# INPUT_POWER.net
KiCad netlist of a schematic drawn in Altium Designer
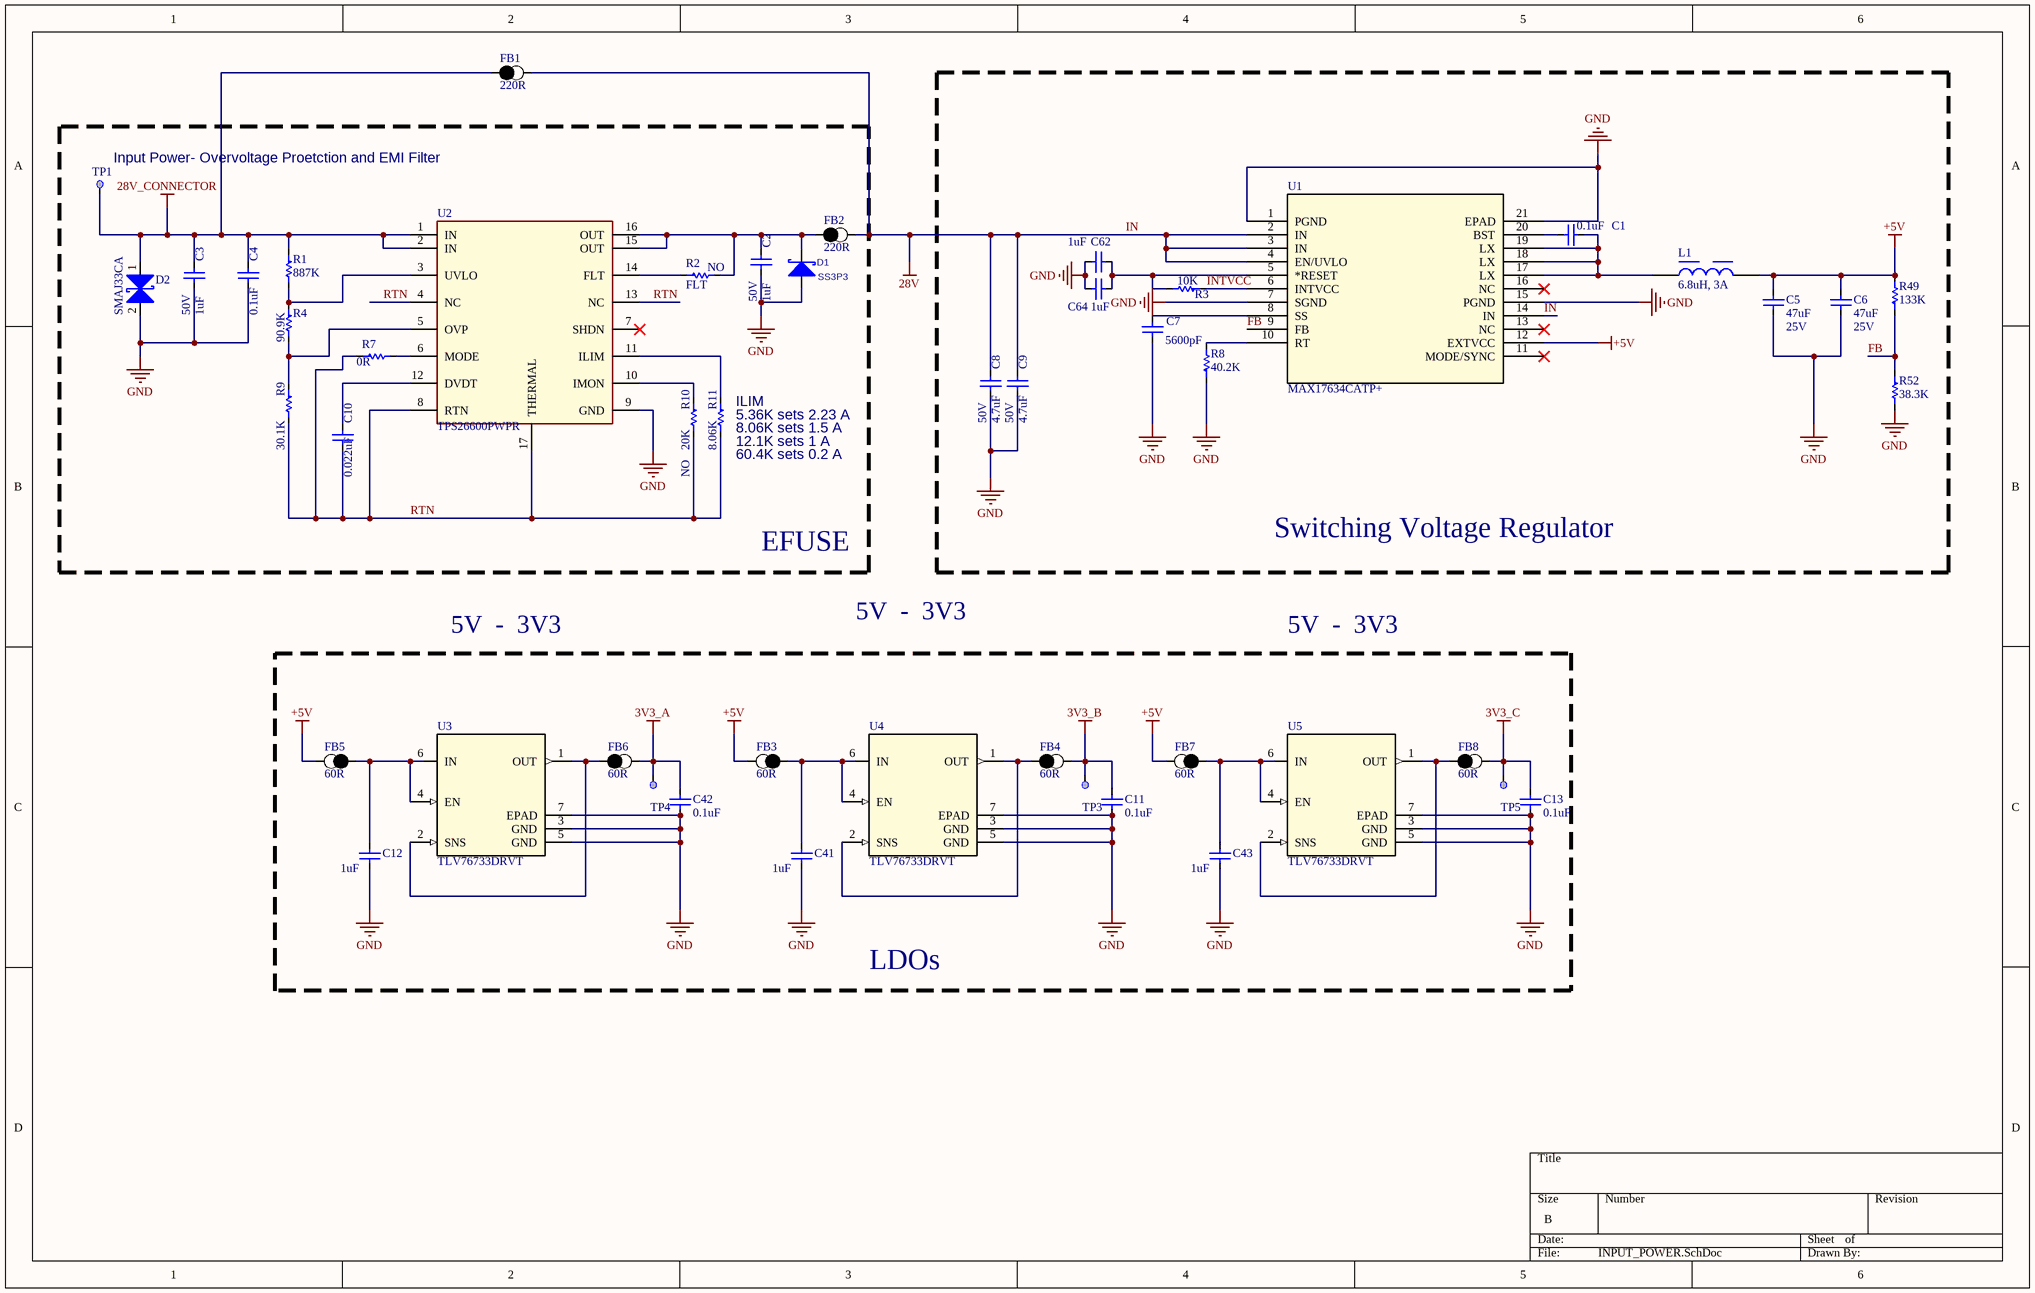
[diagram p0: INPUT_POWER.SchDoc]

(export (version "E")
  (design (tool "Eeschema 10.0.6"))
  (components
    (comp (ref "C1")
      (value "0.1uF")
      (footprint "CAPC1005-0402X55N")
      (description "CAP CER 0.1UF 16V X7R 0402")
      (fields (field (name "MANUFACTURER") "Samsung Electro-Mechanics") (field (name "VOLTAGE") "16V"))
      (libsource (lib "ANTSIS_PASSIVE") (part "CAP 0.1uF_0402"))
    )
    (comp (ref "C2")
      (value "1uF")
      (footprint "CAPC2012-0805X80N")
      (description "CAP CER 1UF 50V X5R 0805")
      (fields
        (field (name "MANUFACTURER") "Taiyo Yuden")
        (field (name "VOLTAGE") "50V")
        (field (name "TOLERANCE") "-55°C ~ 125°C")
      )
      (libsource (lib "capacitor") (part "Capacitor Ceramic"))
    )
    (comp (ref "C3")
      (value "1uF")
      (footprint "CAPC2012-0805X80N")
      (description "CAP CER 1UF 50V X5R 0805")
      (fields
        (field (name "MANUFACTURER") "Taiyo Yuden")
        (field (name "VOLTAGE") "50V")
        (field (name "TOLERANCE") "-55°C ~ 125°C")
      )
      (libsource (lib "capacitor") (part "Capacitor Ceramic"))
    )
    (comp (ref "C4")
      (value "0.1uF")
      (footprint "CAPC2012-0805X110N")
      (description "CAP CER 0.1UF 100V X7R 0805")
      (fields (field (name "MANUFACTURER") "Murata Electronics") (field (name "VOLTAGE") "100V"))
      (libsource (lib "capacitor") (part "Capacitor Ceramic"))
    )
    (comp (ref "C5")
      (value "47uF")
      (footprint "CAPC2012-0805X150N")
      (description "CAP CER 22UF 25V X5R 0805")
      (fields
        (field (name "MANUFACTURER") "Murata Electronics")
        (field (name "TOLERANCE") "-55°C ~ 85°C")
        (field (name "VOLTAGE") "25V")
      )
      (libsource (lib "Video_Encoder_SDI") (part "CAP CER 22UF 0805 25V"))
    )
    (comp (ref "C6")
      (value "47uF")
      (footprint "CAPC2012-0805X150N")
      (description "CAP CER 22UF 25V X5R 0805")
      (fields
        (field (name "MANUFACTURER") "Murata Electronics")
        (field (name "TOLERANCE") "-55°C ~ 85°C")
        (field (name "VOLTAGE") "25V")
      )
      (libsource (lib "Video_Encoder_SDI") (part "CAP CER 22UF 0805 25V"))
    )
    (comp (ref "C7")
      (value "5600pF")
      (footprint "CAPC1005-0402X55N")
      (description "CAP CER 5600PF 25V X7R 0402")
      (fields (field (name "MANUFACTURER") "Murata Electronics") (field (name "VOLTAGE") "25V"))
      (libsource (lib "ANTSIS_PASSIVE") (part "CAP 10nF_0402"))
    )
    (comp (ref "C8")
      (value "4.7uF")
      (footprint "CAPC2012-0805X80N")
      (description "CAP CER 1UF 50V X5R 0805")
      (fields
        (field (name "MANUFACTURER") "Taiyo Yuden")
        (field (name "VOLTAGE") "50V")
        (field (name "TOLERANCE") "-55°C ~ 125°C")
      )
      (libsource (lib "capacitor") (part "Capacitor Ceramic"))
    )
    (comp (ref "C9")
      (value "4.7uF")
      (footprint "CAPC2012-0805X80N")
      (description "CAP CER 1UF 50V X5R 0805")
      (fields
        (field (name "MANUFACTURER") "Taiyo Yuden")
        (field (name "VOLTAGE") "50V")
        (field (name "TOLERANCE") "-55°C ~ 125°C")
      )
      (libsource (lib "capacitor") (part "Capacitor Ceramic"))
    )
    (comp (ref "C10")
      (value "0.022uF")
      (footprint "CAPC1608-0603X90N")
      (description "CAP CER 0.022UF 16V X7R 0603")
      (fields (field (name "MANUFACTURER") "Yageo") (field (name "VOLTAGE") "16V"))
      (libsource (lib "capacitor") (part "Capacitor Ceramic"))
    )
    (comp (ref "C11")
      (value "0.1uF")
      (footprint "CAPC1608-0603X90N")
      (description "CAP CER 0.1UF 50V X7R 0603")
      (fields (field (name "MANUFACTURER") "Samsung Electro-Mechanics") (field (name "VOLTAGE") "50V"))
      (libsource (lib "ANTSIS_PASSIVE") (part "CAP 0.1uF"))
    )
    (comp (ref "C12")
      (value "1uF")
      (footprint "CAPC1608-0603X90N")
      (description "CAP CER 1UF 25V X7R 0603")
      (fields (field (name "MANUFACTURER") "Samsung Electro-Mechanics") (field (name "VOLTAGE") "25V"))
      (libsource (lib "ANTSIS_PASSIVE") (part "CAP 1uF"))
    )
    (comp (ref "C13")
      (value "0.1uF")
      (footprint "CAPC1608-0603X90N")
      (description "CAP CER 0.1UF 50V X7R 0603")
      (fields (field (name "MANUFACTURER") "Samsung Electro-Mechanics") (field (name "VOLTAGE") "50V"))
      (libsource (lib "ANTSIS_PASSIVE") (part "CAP 0.1uF"))
    )
    (comp (ref "C41")
      (value "1uF")
      (footprint "CAPC1608-0603X90N")
      (description "CAP CER 1UF 25V X7R 0603")
      (fields (field (name "MANUFACTURER") "Samsung Electro-Mechanics") (field (name "VOLTAGE") "25V"))
      (libsource (lib "ANTSIS_PASSIVE") (part "CAP 1uF"))
    )
    (comp (ref "C42")
      (value "0.1uF")
      (footprint "CAPC1608-0603X90N")
      (description "CAP CER 0.1UF 50V X7R 0603")
      (fields (field (name "MANUFACTURER") "Samsung Electro-Mechanics") (field (name "VOLTAGE") "50V"))
      (libsource (lib "ANTSIS_PASSIVE") (part "CAP 0.1uF"))
    )
    (comp (ref "C43")
      (value "1uF")
      (footprint "CAPC1608-0603X90N")
      (description "CAP CER 1UF 25V X7R 0603")
      (fields (field (name "MANUFACTURER") "Samsung Electro-Mechanics") (field (name "VOLTAGE") "25V"))
      (libsource (lib "ANTSIS_PASSIVE") (part "CAP 1uF"))
    )
    (comp (ref "C62")
      (value "1uF")
      (footprint "CAPC1608-0603X90N")
      (description "CAP CER 1UF 25V X7R 0603")
      (fields (field (name "MANUFACTURER") "Samsung Electro-Mechanics") (field (name "VOLTAGE") "25V"))
      (libsource (lib "ANTSIS_PASSIVE") (part "CAP 1uF"))
    )
    (comp (ref "C64")
      (value "1uF")
      (footprint "CAPC1608-0603X90N")
      (description "CAP CER 1UF 25V X7R 0603")
      (fields (field (name "MANUFACTURER") "Samsung Electro-Mechanics") (field (name "VOLTAGE") "25V"))
      (libsource (lib "ANTSIS_PASSIVE") (part "CAP 1uF"))
    )
    (comp (ref "D1")
      (value "SS3P3")
      (footprint "DO-220AA (SMP)")
      (description "DIODE SCHOTTKY 40V 3A DO220AA")
      (fields
        (field (name "MANUFACTURER") "Vishay Semiconductor Diodes Division")
        (field (name "VOLTAGE") "40V")
      )
      (libsource (lib "Ixora") (part "D-Vishay-SS3P3-E3/84A-Schottky"))
    )
    (comp (ref "D2")
      (value "SMAJ33CA")
      (footprint "DO-214AC")
      (description "TVS DIODE 33V 53.3V DO214AC")
      (fields
        (field (name "MANUFACTURER") "ON Semiconductor")
        (field (name "TOLERANCE") "-65°C ~ 150°C (TJ)")
      )
      (libsource (lib "ANTSIS_DIODE_TRANSISTOR") (part "SMAJ33CA"))
    )
    (comp (ref "FB1")
      (value "220R")
      (footprint "INDC2012-0805X90N")
      (description "FERRITE BEAD 220 OHM 0805 1LN")
      (fields (field (name "MANUFACTURER") "Murata Electronics") (field (name "VOLTAGE") "2A"))
      (libsource (lib "Inductors & Transformers") (part "Inductor EMI suppresion"))
    )
    (comp (ref "FB2")
      (value "220R")
      (footprint "INDC2012-0805X90N")
      (description "FERRITE BEAD 220 OHM 0805 1LN")
      (fields (field (name "MANUFACTURER") "Murata Electronics") (field (name "VOLTAGE") "2A"))
      (libsource (lib "Inductors & Transformers") (part "Inductor EMI suppresion"))
    )
    (comp (ref "FB3")
      (value "60R")
      (footprint "INDC1608-0603X80N")
      (description "FERRITE BEAD 60 OHM 0603 1LN")
      (fields (field (name "MANUFACTURER") "Würth Elektronik") (field (name "TOLERANCE") "-55°C ~ 125°C"))
      (libsource (lib "ANTSIS_PASSIVE") (part "FERRITE 60R 3A"))
    )
    (comp (ref "FB4")
      (value "60R")
      (footprint "INDC1608-0603X80N")
      (description "FERRITE BEAD 60 OHM 0603 1LN")
      (fields (field (name "MANUFACTURER") "Würth Elektronik") (field (name "TOLERANCE") "-55°C ~ 125°C"))
      (libsource (lib "ANTSIS_PASSIVE") (part "FERRITE 60R 3A"))
    )
    (comp (ref "FB5")
      (value "60R")
      (footprint "INDC1608-0603X80N")
      (description "FERRITE BEAD 60 OHM 0603 1LN")
      (fields (field (name "MANUFACTURER") "Würth Elektronik") (field (name "TOLERANCE") "-55°C ~ 125°C"))
      (libsource (lib "ANTSIS_PASSIVE") (part "FERRITE 60R 3A"))
    )
    (comp (ref "FB6")
      (value "60R")
      (footprint "INDC1608-0603X80N")
      (description "FERRITE BEAD 60 OHM 0603 1LN")
      (fields (field (name "MANUFACTURER") "Würth Elektronik") (field (name "TOLERANCE") "-55°C ~ 125°C"))
      (libsource (lib "ANTSIS_PASSIVE") (part "FERRITE 60R 3A"))
    )
    (comp (ref "FB7")
      (value "60R")
      (footprint "INDC1608-0603X80N")
      (description "FERRITE BEAD 60 OHM 0603 1LN")
      (fields (field (name "MANUFACTURER") "Würth Elektronik") (field (name "TOLERANCE") "-55°C ~ 125°C"))
      (libsource (lib "ANTSIS_PASSIVE") (part "FERRITE 60R 3A"))
    )
    (comp (ref "FB8")
      (value "60R")
      (footprint "INDC1608-0603X80N")
      (description "FERRITE BEAD 60 OHM 0603 1LN")
      (fields (field (name "MANUFACTURER") "Würth Elektronik") (field (name "TOLERANCE") "-55°C ~ 125°C"))
      (libsource (lib "ANTSIS_PASSIVE") (part "FERRITE 60R 3A"))
    )
    (comp (ref "L1")
      (value "6.8uH, 3A")
      (footprint "WE-MAIA_4030")
      (description "WE-MAIA SMT Power Inductor, size 4030, 6.8uH, 3A, 74mOhm")
      (fields
        (field (name "MANUFACTURER PART NUMBER") "78438357068")
        (field (name "MANUFACTURER") "Wurth Elektronik")
      )
      (libsource (lib "Altium_WE-MAIA (rev20c)") (part "78438357068"))
    )
    (comp (ref "R1")
      (value "887K")
      (footprint "RESC1608-0603X50N")
      (description "RES SMD 887K OHM 1% 1/10W 0603")
      (fields (field (name "MANUFACTURER") "Vishay Dale") (field (name "TOLERANCE") "-55°C ~ 155°C"))
      (libsource (lib "resistor") (part "Resistor SMD"))
    )
    (comp (ref "R2")
      (value "FLT")
      (footprint "RESC1608-0603X50N")
      (description "RES SMD 12.1K OHM 1% 1/10W 0603")
      (fields (field (name "POPULATED") "NO") (field (name "TOLERANCE") "-55°C ~ 155°C"))
      (libsource (lib "resistor") (part "Resistor SMD"))
    )
    (comp (ref "R3")
      (value "10K")
      (footprint "RESC1005-0402X35N")
      (description "RES SMD 10K OHM 1% 1/10W 0402")
      (fields (field (name "MANUFACTURER") "Yageo") (field (name "TOLERANCE") "5%"))
      (libsource (lib "ANTSIS_PASSIVE") (part "RESISTOR 10K_0402"))
    )
    (comp (ref "R4")
      (value "90.9K")
      (footprint "RESC1608-0603X50N")
      (description "RES SMD 90.9K OHM 1% 1/10W 0603")
      (fields (field (name "MANUFACTURER") "Vishay Dale") (field (name "TOLERANCE") "-55°C ~ 155°C"))
      (libsource (lib "resistor") (part "Resistor SMD"))
    )
    (comp (ref "R7")
      (value "0R")
      (footprint "RESC1608-0603X50N")
      (description "RES SMD 0 OHM JUMPER 1/10W 0603")
      (fields (field (name "MANUFACTURER") "Yageo") (field (name "TOLERANCE") "-55°C ~ 155°C"))
      (libsource (lib "resistor") (part "Resistor SMD"))
    )
    (comp (ref "R8")
      (value "40.2K")
      (footprint "RESC1608-0603X50N")
      (description "RES SMD 0 OHM JUMPER 1/10W 0603")
      (fields (field (name "MANUFACTURER") "Yageo"))
      (libsource (lib "ANTSIS_PASSIVE") (part "RESISTOR 0R"))
    )
    (comp (ref "R9")
      (value "30.1K")
      (footprint "RESC1608-0603X50N")
      (description "RES SMD 30.1K OHM 1% 1/10W 0603")
      (fields (field (name "MANUFACTURER") "Vishay Dale") (field (name "TOLERANCE") "-55°C ~ 155°C"))
      (libsource (lib "resistor") (part "Resistor SMD"))
    )
    (comp (ref "R10")
      (value "20K")
      (footprint "RESC1608-0603X50N")
      (description "RES SMD 20K OHM 1% 1/10W 0603")
      (fields
        (field (name "POPULATED") "NO")
        (field (name "MANUFACTURER") "Vishay Dale")
        (field (name "TOLERANCE") "-55°C ~ 155°C")
      )
      (libsource (lib "resistor") (part "Resistor SMD"))
    )
    (comp (ref "R11")
      (value "8.06K")
      (footprint "RESC1608-0603X50N")
      (description "RES SMD 8.06 OHM 1% 1/10W 0603")
      (fields (field (name "MANUFACTURER") "Vishay Dale") (field (name "TOLERANCE") "-55°C ~ 155°C"))
      (libsource (lib "resistor") (part "Resistor SMD"))
    )
    (comp (ref "R49")
      (value "133K")
      (footprint "RESC1608-0603X50N")
      (description "RES SMD 133K OHM 1% 1/4W 0603")
      (fields (field (name "MANUFACTURER") "Vishay Dale") (field (name "TOLERANCE") "1%"))
      (libsource (lib "ANTSIS_PASSIVE") (part "RESISTOR 143K"))
    )
    (comp (ref "R52")
      (value "38.3K")
      (footprint "RESC1608-0603X50N")
      (description "RES 38.3K OHM 1% 1/10W 0603")
      (fields (field (name "MANUFACTURER") "Stackpole Electronics Inc") (field (name "TOLERANCE") "1%"))
      (libsource (lib "ANTSIS_PASSIVE") (part "RESISTOR 143K"))
    )
    (comp (ref "TP1")
      (value "TP")
      (footprint "TP-OCTAGONAL")
      (description "Test point")
      (libsource (lib "ANTSIS_AUX_PART") (part "TP"))
    )
    (comp (ref "TP3")
      (value "TP")
      (footprint "TP-OCTAGONAL")
      (description "Test point")
      (libsource (lib "ANTSIS_AUX_PART") (part "TP"))
    )
    (comp (ref "TP4")
      (value "TP")
      (footprint "TP-OCTAGONAL")
      (description "Test point")
      (libsource (lib "ANTSIS_AUX_PART") (part "TP"))
    )
    (comp (ref "TP5")
      (value "TP")
      (footprint "TP-OCTAGONAL")
      (description "Test point")
      (libsource (lib "ANTSIS_AUX_PART") (part "TP"))
    )
    (comp (ref "U1")
      (value "MAX17634CATP+")
      (footprint "max17633")
      (description "IC REG BUCK ADJ 4.25A")
      (fields
        (field (name "MANUFACTURER_PART_NUMBER") "MAX17633CATP+")
        (field (name "COPYRIGHT") "Copyright (C) 2021 Ultra Librarian. All rights reserved.")
      )
      (libsource (lib "MAX17633CATP&plus_") (part "MAX17633CATP+"))
    )
    (comp (ref "U2")
      (value "TPS26600PWPR")
      (footprint "TSSOP65P640-16N-2.74MM T.PAD")
      (description "IC PWR MGMT EFUSE 60V 16HTSSOP")
      (fields
        (field (name "MANUFACTURER") "Texas Instruments")
        (field (name "TOLERANCE") "-40°C ~ 125°C (TJ)")
      )
      (libsource (lib "TI") (part "TPS26600"))
    )
    (comp (ref "U3")
      (value "TLV76733DRVT")
      (footprint "SON65P200X200X80-7N")
      (description "No Description Available")
      (fields (field (name "COPYRIGHT") "Copyright (C) 2021 Ultra Librarian. All rights reserved."))
      (libsource (lib "TLV76733DRVT") (part "TLV76733DRVT"))
    )
    (comp (ref "U4")
      (value "TLV76733DRVT")
      (footprint "SON65P200X200X80-7N")
      (description "No Description Available")
      (fields (field (name "COPYRIGHT") "Copyright (C) 2021 Ultra Librarian. All rights reserved."))
      (libsource (lib "TLV76733DRVT") (part "TLV76733DRVT"))
    )
    (comp (ref "U5")
      (value "TLV76733DRVT")
      (footprint "SON65P200X200X80-7N")
      (description "No Description Available")
      (fields (field (name "COPYRIGHT") "Copyright (C) 2021 Ultra Librarian. All rights reserved."))
      (libsource (lib "TLV76733DRVT") (part "TLV76733DRVT"))
    )
  )
  (nets
    (net (code "1") (name "+5V") (class "Default")
      (node (ref "C5") (pin "2") (pinfunction "2_2") (pintype "passive"))
      (node (ref "C6") (pin "2") (pinfunction "2_2") (pintype "passive"))
      (node (ref "FB3") (pin "2") (pinfunction "2_2") (pintype "passive"))
      (node (ref "FB5") (pin "2") (pinfunction "2_2") (pintype "passive"))
      (node (ref "FB7") (pin "2") (pinfunction "2_2") (pintype "passive"))
      (node (ref "L1") (pin "2") (pinfunction "2_2") (pintype "passive"))
      (node (ref "R49") (pin "2") (pinfunction "2_2") (pintype "passive"))
      (node (ref "U1") (pin "12") (pinfunction "EXTVCC_12") (pintype "passive"))
    )
    (net (code "2") (name "/FB") (class "Default")
      (node (ref "R49") (pin "1") (pinfunction "1_1") (pintype "passive"))
      (node (ref "R52") (pin "1") (pinfunction "1_1") (pintype "passive"))
      (node (ref "U1") (pin "9") (pinfunction "FB_9") (pintype "passive"))
    )
    (net (code "3") (name "/INTVCC") (class "Default")
      (node (ref "R3") (pin "1") (pinfunction "1_1") (pintype "passive"))
      (node (ref "U1") (pin "6") (pinfunction "INTVCC_6") (pintype "passive"))
    )
    (net (code "4") (name "/RTN") (class "Default")
      (node (ref "C10") (pin "1") (pinfunction "1_1") (pintype "passive"))
      (node (ref "R10") (pin "2") (pinfunction "2_2") (pintype "passive"))
      (node (ref "R11") (pin "2") (pinfunction "2_2") (pintype "passive"))
      (node (ref "R7") (pin "1") (pinfunction "1_1") (pintype "passive"))
      (node (ref "R9") (pin "2") (pinfunction "2_2") (pintype "passive"))
      (node (ref "U2") (pin "13") (pinfunction "NC_13") (pintype "passive"))
      (node (ref "U2") (pin "17") (pinfunction "THERMAL_17") (pintype "power_in"))
      (node (ref "U2") (pin "4") (pinfunction "NC_4") (pintype "passive"))
      (node (ref "U2") (pin "8") (pinfunction "RTN_8") (pintype "passive"))
    )
    (net (code "5") (name "3V3_A") (class "Default")
      (node (ref "C42") (pin "2") (pinfunction "2_2") (pintype "passive"))
      (node (ref "FB6") (pin "2") (pinfunction "2_2") (pintype "passive"))
      (node (ref "TP4") (pin "1") (pinfunction "1_1") (pintype "passive"))
    )
    (net (code "6") (name "3V3_B") (class "Default")
      (node (ref "C11") (pin "2") (pinfunction "2_2") (pintype "passive"))
      (node (ref "FB4") (pin "2") (pinfunction "2_2") (pintype "passive"))
      (node (ref "TP3") (pin "1") (pinfunction "1_1") (pintype "passive"))
    )
    (net (code "7") (name "3V3_C") (class "Default")
      (node (ref "C13") (pin "2") (pinfunction "2_2") (pintype "passive"))
      (node (ref "FB8") (pin "2") (pinfunction "2_2") (pintype "passive"))
      (node (ref "TP5") (pin "1") (pinfunction "1_1") (pintype "passive"))
    )
    (net (code "8") (name "28V") (class "Default")
      (node (ref "C8") (pin "1") (pinfunction "1_1") (pintype "passive"))
      (node (ref "C9") (pin "1") (pinfunction "1_1") (pintype "passive"))
      (node (ref "FB1") (pin "2") (pinfunction "2_2") (pintype "passive"))
      (node (ref "FB2") (pin "2") (pinfunction "2_2") (pintype "passive"))
      (node (ref "U1") (pin "14") (pinfunction "IN_14") (pintype "passive"))
      (node (ref "U1") (pin "2") (pinfunction "IN_2") (pintype "passive"))
      (node (ref "U1") (pin "3") (pinfunction "IN_3") (pintype "passive"))
      (node (ref "U1") (pin "4") (pinfunction "EN/UVLO_4") (pintype "passive"))
    )
    (net (code "9") (name "28V_CONNECTOR") (class "Default")
      (node (ref "C3") (pin "1") (pinfunction "1_1") (pintype "passive"))
      (node (ref "C4") (pin "2") (pinfunction "2_2") (pintype "passive"))
      (node (ref "D2") (pin "1") (pinfunction "K_1") (pintype "passive"))
      (node (ref "FB1") (pin "1") (pinfunction "1_1") (pintype "passive"))
      (node (ref "R1") (pin "1") (pinfunction "1_1") (pintype "passive"))
      (node (ref "TP1") (pin "1") (pinfunction "1_1") (pintype "passive"))
      (node (ref "U2") (pin "1") (pinfunction "IN_1") (pintype "power_in"))
      (node (ref "U2") (pin "2") (pinfunction "IN_2") (pintype "power_in"))
    )
    (net (code "10") (name "GND") (class "Default")
      (node (ref "C11") (pin "1") (pinfunction "1_1") (pintype "passive"))
      (node (ref "C12") (pin "1") (pinfunction "1_1") (pintype "passive"))
      (node (ref "C13") (pin "1") (pinfunction "1_1") (pintype "passive"))
      (node (ref "C2") (pin "2") (pinfunction "2_2") (pintype "passive"))
      (node (ref "C3") (pin "2") (pinfunction "2_2") (pintype "passive"))
      (node (ref "C4") (pin "1") (pinfunction "1_1") (pintype "passive"))
      (node (ref "C41") (pin "1") (pinfunction "1_1") (pintype "passive"))
      (node (ref "C42") (pin "1") (pinfunction "1_1") (pintype "passive"))
      (node (ref "C43") (pin "1") (pinfunction "1_1") (pintype "passive"))
      (node (ref "C5") (pin "1") (pinfunction "1_1") (pintype "passive"))
      (node (ref "C6") (pin "1") (pinfunction "1_1") (pintype "passive"))
      (node (ref "C62") (pin "2") (pinfunction "2_2") (pintype "passive"))
      (node (ref "C64") (pin "2") (pinfunction "2_2") (pintype "passive"))
      (node (ref "C7") (pin "1") (pinfunction "1_1") (pintype "passive"))
      (node (ref "C8") (pin "2") (pinfunction "2_2") (pintype "passive"))
      (node (ref "C9") (pin "2") (pinfunction "2_2") (pintype "passive"))
      (node (ref "D1") (pin "2") (pinfunction "2_2") (pintype "passive"))
      (node (ref "D2") (pin "2") (pinfunction "A_2") (pintype "passive"))
      (node (ref "R52") (pin "2") (pinfunction "2_2") (pintype "passive"))
      (node (ref "R8") (pin "1") (pinfunction "1_1") (pintype "passive"))
      (node (ref "U1") (pin "1") (pinfunction "PGND_1") (pintype "passive"))
      (node (ref "U1") (pin "15") (pinfunction "PGND_15") (pintype "passive"))
      (node (ref "U1") (pin "21") (pinfunction "EPAD_21") (pintype "passive"))
      (node (ref "U1") (pin "7") (pinfunction "SGND_7") (pintype "passive"))
      (node (ref "U2") (pin "9") (pinfunction "GND_9") (pintype "power_in"))
      (node (ref "U3") (pin "3") (pinfunction "GND_3") (pintype "power_in"))
      (node (ref "U3") (pin "5") (pinfunction "GND_5") (pintype "power_in"))
      (node (ref "U3") (pin "7") (pinfunction "EPAD_7") (pintype "passive"))
      (node (ref "U4") (pin "3") (pinfunction "GND_3") (pintype "power_in"))
      (node (ref "U4") (pin "5") (pinfunction "GND_5") (pintype "power_in"))
      (node (ref "U4") (pin "7") (pinfunction "EPAD_7") (pintype "passive"))
      (node (ref "U5") (pin "3") (pinfunction "GND_3") (pintype "power_in"))
      (node (ref "U5") (pin "5") (pinfunction "GND_5") (pintype "power_in"))
      (node (ref "U5") (pin "7") (pinfunction "EPAD_7") (pintype "passive"))
    )
    (net (code "11") (name "Net-(C1-Pad2)") (class "Default")
      (node (ref "C1") (pin "2") (pinfunction "2_2") (pintype "passive"))
      (node (ref "L1") (pin "1") (pinfunction "1_1") (pintype "passive"))
      (node (ref "U1") (pin "17") (pinfunction "LX_17") (pintype "passive"))
      (node (ref "U1") (pin "18") (pinfunction "LX_18") (pintype "passive"))
      (node (ref "U1") (pin "19") (pinfunction "LX_19") (pintype "passive"))
    )
    (net (code "12") (name "Net-(C2-Pad1)") (class "Default")
      (node (ref "C2") (pin "1") (pinfunction "1_1") (pintype "passive"))
      (node (ref "D1") (pin "1") (pinfunction "1_1") (pintype "passive"))
      (node (ref "FB2") (pin "1") (pinfunction "1_1") (pintype "passive"))
      (node (ref "R2") (pin "2") (pinfunction "2_2") (pintype "passive"))
      (node (ref "U2") (pin "15") (pinfunction "OUT_15") (pintype "power_in"))
      (node (ref "U2") (pin "16") (pinfunction "OUT_16") (pintype "power_in"))
    )
    (net (code "13") (name "Net-(U1-*RESET)") (class "Default")
      (node (ref "C62") (pin "1") (pinfunction "1_1") (pintype "passive"))
      (node (ref "C64") (pin "1") (pinfunction "1_1") (pintype "passive"))
      (node (ref "R3") (pin "2") (pinfunction "2_2") (pintype "passive"))
      (node (ref "U1") (pin "5") (pinfunction "*RESET_5") (pintype "passive"))
    )
    (net (code "14") (name "Net-(U1-BST)") (class "Default")
      (node (ref "C1") (pin "1") (pinfunction "1_1") (pintype "passive"))
      (node (ref "U1") (pin "20") (pinfunction "BST_20") (pintype "passive"))
    )
    (net (code "15") (name "Net-(U1-RT)") (class "Default")
      (node (ref "R8") (pin "2") (pinfunction "2_2") (pintype "passive"))
      (node (ref "U1") (pin "10") (pinfunction "RT_10") (pintype "passive"))
    )
    (net (code "16") (name "Net-(U1-SS)") (class "Default")
      (node (ref "C7") (pin "2") (pinfunction "2_2") (pintype "passive"))
      (node (ref "U1") (pin "8") (pinfunction "SS_8") (pintype "passive"))
    )
    (net (code "17") (name "Net-(U2-DVDT)") (class "Default")
      (node (ref "C10") (pin "2") (pinfunction "2_2") (pintype "passive"))
      (node (ref "U2") (pin "12") (pinfunction "DVDT_12") (pintype "passive"))
    )
    (net (code "18") (name "Net-(U2-FLT)") (class "Default")
      (node (ref "R2") (pin "1") (pinfunction "1_1") (pintype "passive"))
      (node (ref "U2") (pin "14") (pinfunction "FLT_14") (pintype "passive"))
    )
    (net (code "19") (name "Net-(U2-ILIM)") (class "Default")
      (node (ref "R11") (pin "1") (pinfunction "1_1") (pintype "passive"))
      (node (ref "U2") (pin "11") (pinfunction "ILIM_11") (pintype "passive"))
    )
    (net (code "20") (name "Net-(U2-IMON)") (class "Default")
      (node (ref "R10") (pin "1") (pinfunction "1_1") (pintype "passive"))
      (node (ref "U2") (pin "10") (pinfunction "IMON_10") (pintype "passive"))
    )
    (net (code "21") (name "Net-(U2-MODE)") (class "Default")
      (node (ref "R7") (pin "2") (pinfunction "2_2") (pintype "passive"))
      (node (ref "U2") (pin "6") (pinfunction "MODE_6") (pintype "passive"))
    )
    (net (code "22") (name "Net-(U2-OVP)") (class "Default")
      (node (ref "R4") (pin "2") (pinfunction "2_2") (pintype "passive"))
      (node (ref "R9") (pin "1") (pinfunction "1_1") (pintype "passive"))
      (node (ref "U2") (pin "5") (pinfunction "OVP_5") (pintype "passive"))
    )
    (net (code "23") (name "Net-(U2-UVLO)") (class "Default")
      (node (ref "R1") (pin "2") (pinfunction "2_2") (pintype "passive"))
      (node (ref "R4") (pin "1") (pinfunction "1_1") (pintype "passive"))
      (node (ref "U2") (pin "3") (pinfunction "UVLO_3") (pintype "passive"))
    )
    (net (code "24") (name "Net-(U3-EN)") (class "Default")
      (node (ref "C12") (pin "2") (pinfunction "2_2") (pintype "passive"))
      (node (ref "FB5") (pin "1") (pinfunction "1_1") (pintype "passive"))
      (node (ref "U3") (pin "4") (pinfunction "EN_4") (pintype "input"))
      (node (ref "U3") (pin "6") (pinfunction "IN_6") (pintype "power_in"))
    )
    (net (code "25") (name "Net-(U3-OUT)") (class "Default")
      (node (ref "FB6") (pin "1") (pinfunction "1_1") (pintype "passive"))
      (node (ref "U3") (pin "1") (pinfunction "OUT_1") (pintype "output"))
      (node (ref "U3") (pin "2") (pinfunction "SNS_2") (pintype "input"))
    )
    (net (code "26") (name "Net-(U4-EN)") (class "Default")
      (node (ref "C41") (pin "2") (pinfunction "2_2") (pintype "passive"))
      (node (ref "FB3") (pin "1") (pinfunction "1_1") (pintype "passive"))
      (node (ref "U4") (pin "4") (pinfunction "EN_4") (pintype "input"))
      (node (ref "U4") (pin "6") (pinfunction "IN_6") (pintype "power_in"))
    )
    (net (code "27") (name "Net-(U4-OUT)") (class "Default")
      (node (ref "FB4") (pin "1") (pinfunction "1_1") (pintype "passive"))
      (node (ref "U4") (pin "1") (pinfunction "OUT_1") (pintype "output"))
      (node (ref "U4") (pin "2") (pinfunction "SNS_2") (pintype "input"))
    )
    (net (code "28") (name "Net-(U5-EN)") (class "Default")
      (node (ref "C43") (pin "2") (pinfunction "2_2") (pintype "passive"))
      (node (ref "FB7") (pin "1") (pinfunction "1_1") (pintype "passive"))
      (node (ref "U5") (pin "4") (pinfunction "EN_4") (pintype "input"))
      (node (ref "U5") (pin "6") (pinfunction "IN_6") (pintype "power_in"))
    )
    (net (code "29") (name "Net-(U5-OUT)") (class "Default")
      (node (ref "FB8") (pin "1") (pinfunction "1_1") (pintype "passive"))
      (node (ref "U5") (pin "1") (pinfunction "OUT_1") (pintype "output"))
      (node (ref "U5") (pin "2") (pinfunction "SNS_2") (pintype "input"))
    )
    (net (code "30") (name "unconnected-(U1-MODE{slash}SYNC-Pad11)") (class "Default")
      (node (ref "U1") (pin "11") (pinfunction "MODE/SYNC_11") (pintype "passive+no_connect"))
    )
    (net (code "31") (name "unconnected-(U1-NC-Pad13)") (class "Default")
      (node (ref "U1") (pin "13") (pinfunction "NC_13") (pintype "passive+no_connect"))
    )
    (net (code "32") (name "unconnected-(U1-NC-Pad16)") (class "Default")
      (node (ref "U1") (pin "16") (pinfunction "NC_16") (pintype "passive+no_connect"))
    )
    (net (code "33") (name "unconnected-(U2-SHDN-Pad7)") (class "Default")
      (node (ref "U2") (pin "7") (pinfunction "SHDN_7") (pintype "passive+no_connect"))
    )
  )
)
